# RK3566_FLASH_SD_SARADC.net
KiCad netlist of a schematic drawn in Altium Designer
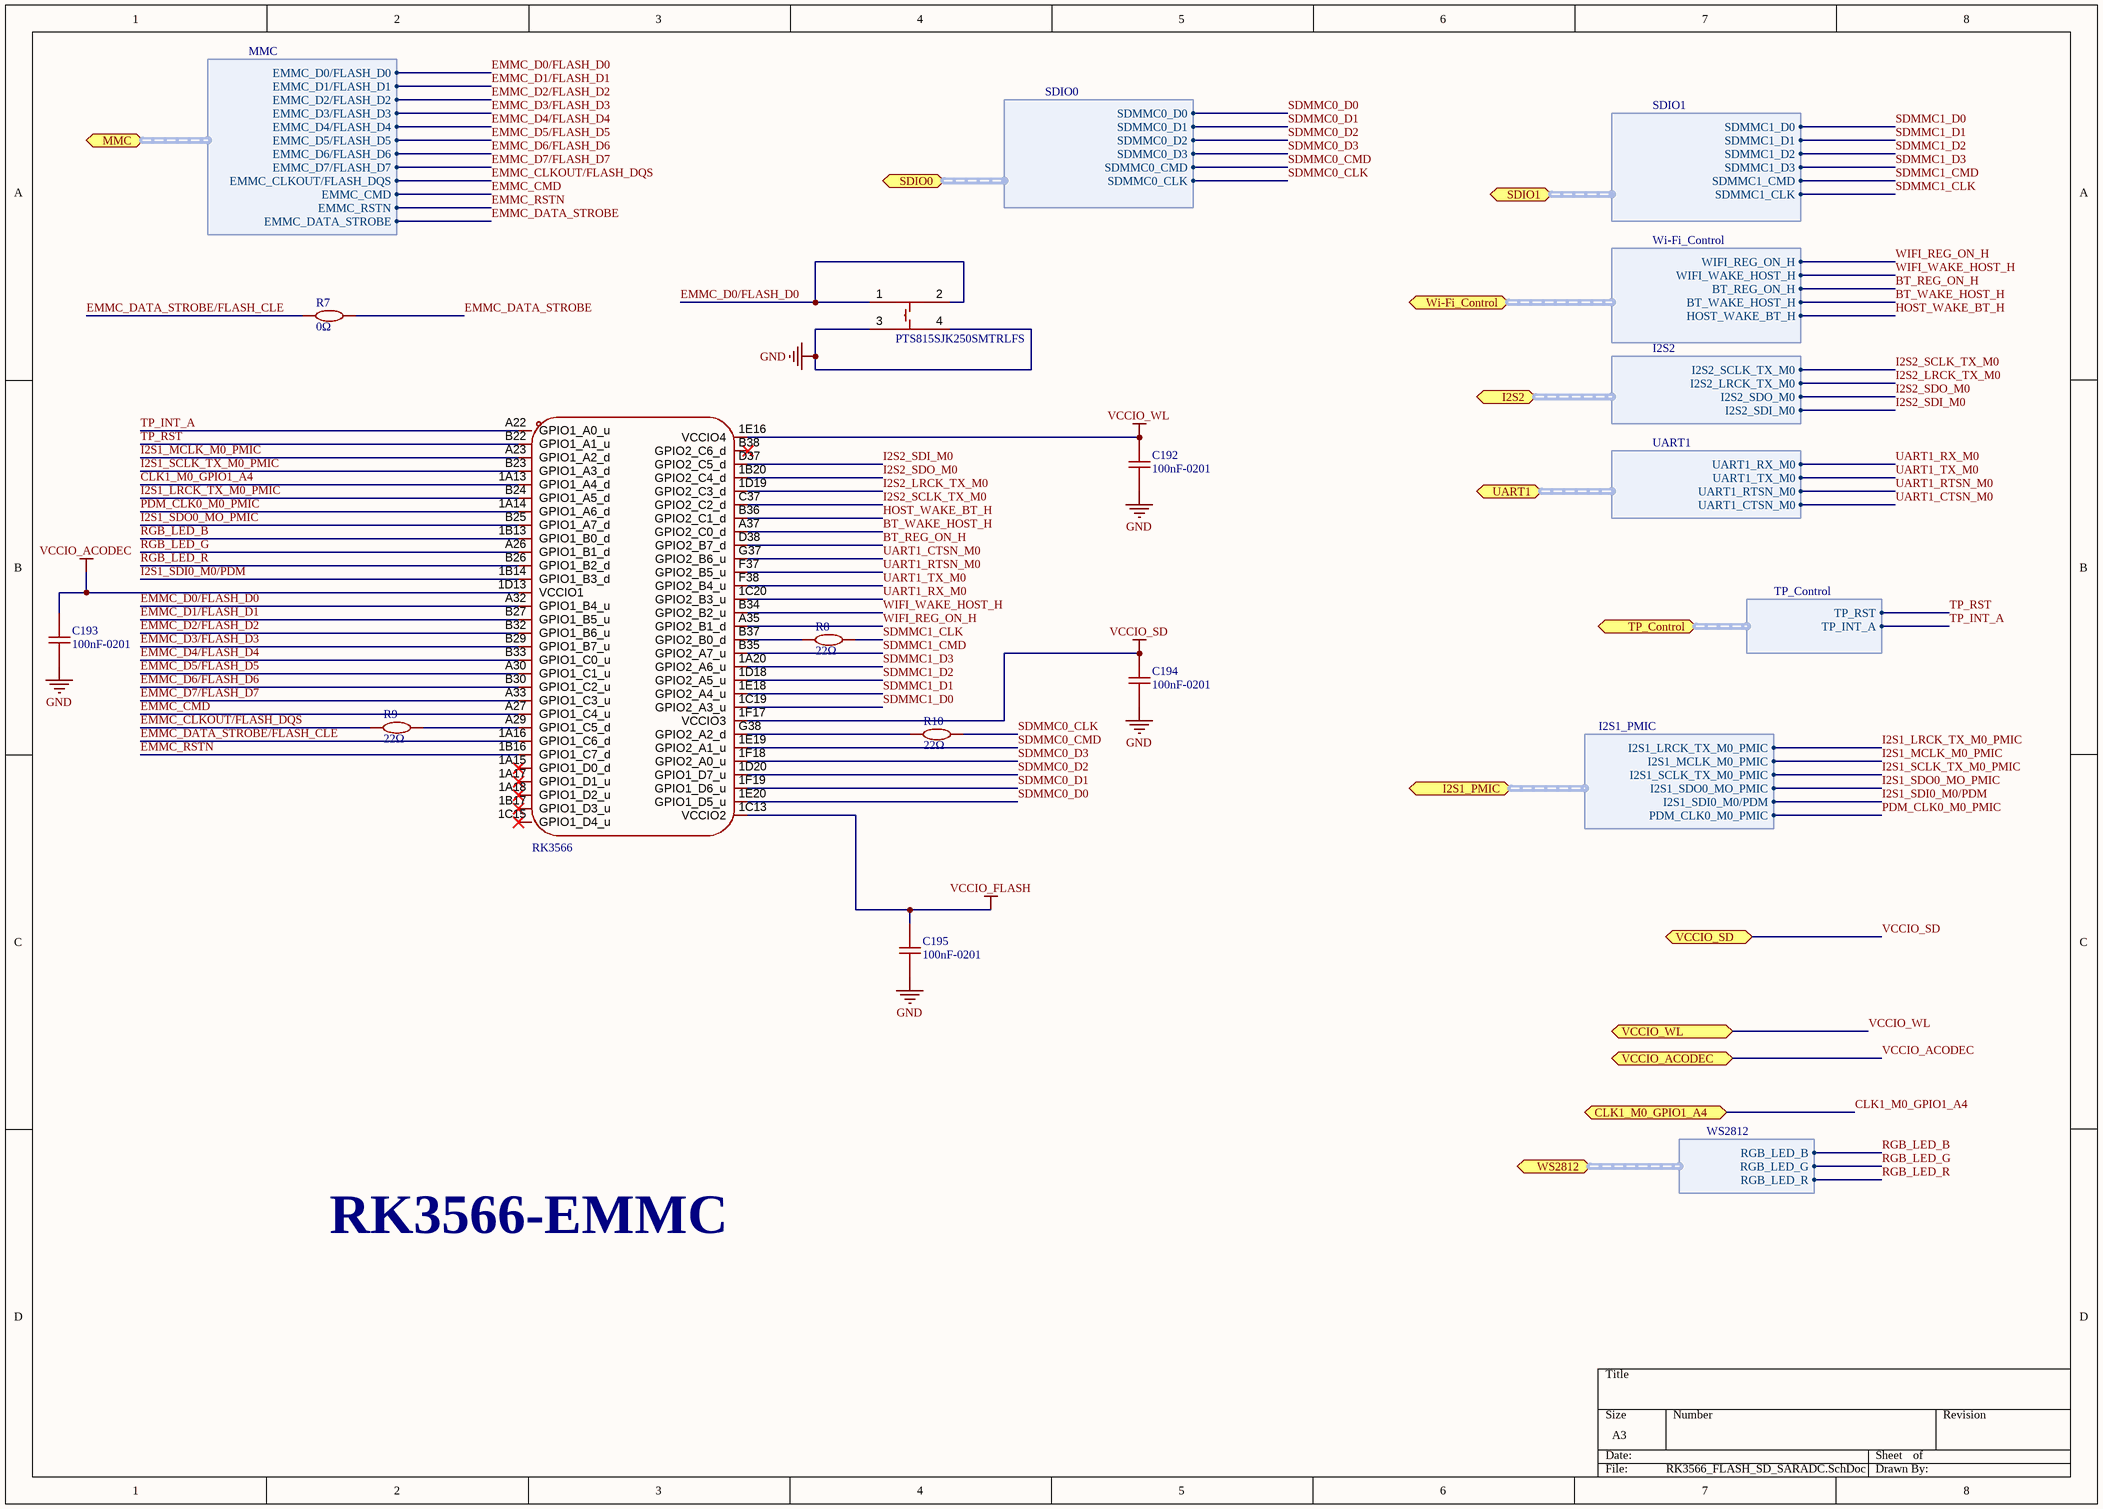
[diagram p0: RK3566_FLASH_SD_SARADC.SchDoc]

(export (version "E")
  (design (tool "Eeschema 10.0.6"))
  (components
    (comp (ref "C192")
      (value "100nF-0201")
      (footprint "C0201")
      (description "CL03A104KO3NNNC")
      (libsource (lib "RLC") (part "100nF-0201"))
    )
    (comp (ref "C193")
      (value "100nF-0201")
      (footprint "C0201")
      (description "CL03A104KO3NNNC")
      (libsource (lib "RLC") (part "100nF-0201"))
    )
    (comp (ref "C194")
      (value "100nF-0201")
      (footprint "C0201")
      (description "CL03A104KO3NNNC")
      (libsource (lib "RLC") (part "100nF-0201"))
    )
    (comp (ref "C195")
      (value "100nF-0201")
      (footprint "C0201")
      (description "CL03A104KO3NNNC")
      (libsource (lib "RLC") (part "100nF-0201"))
    )
    (comp (ref "R7")
      (value "0Ω")
      (footprint "R0402")
      (description "0Ω 62.5mW 50V Thick Film Resistor ±1% 0402 Chip Resistor - Surface Mount ROHS")
      (libsource (lib "RLC") (part "0Ω"))
    )
    (comp (ref "R8")
      (value "22Ω")
      (footprint "R0402")
      (description "62.5mW 33Ω 50V ±100ppm/℃ Thick Film Resistor ±1% 0402 Chip Resistor - Surface Mount ROHS")
      (libsource (lib "RLC") (part "22Ω"))
    )
    (comp (ref "R9")
      (value "22Ω")
      (footprint "R0402")
      (description "62.5mW 33Ω 50V ±100ppm/℃ Thick Film Resistor ±1% 0402 Chip Resistor - Surface Mount ROHS")
      (libsource (lib "RLC") (part "22Ω"))
    )
    (comp (ref "R10")
      (value "22Ω")
      (footprint "R0402")
      (description "62.5mW 33Ω 50V ±100ppm/℃ Thick Film Resistor ±1% 0402 Chip Resistor - Surface Mount ROHS")
      (libsource (lib "RLC") (part "22Ω"))
    )
    (comp (ref "SW4")
      (value "PTS815SJK250SMTRLFS")
      (footprint "SW-SMD_4P-L4.2-W3.3-P2.15-LS5.1")
      (description "4pin 轻触开关 SMD​")
      (libsource (lib "Switch") (part "PTS815SJK250SMTRLFS"))
    )
    (comp (ref "U2")
      (value "RK3566")
      (footprint "BGA-565_L15.5-W14.4-P0.40_RK3566_1")
      (description "BGA-565(15.5x14.4)")
      (libsource (lib "IC") (part "RK3566"))
    )
  )
  (nets
    (net (code "10") (name "/BT_REG_ON_H") (class "Default")
      (node (ref "U2") (pin "D38") (pinfunction "GPIO2_B7_d_D38") (pintype "passive"))
    )
    (net (code "11") (name "/BT_WAKE_HOST_H") (class "Default")
      (node (ref "U2") (pin "A37") (pinfunction "GPIO2_C0_d_A37") (pintype "passive"))
    )
    (net (code "12") (name "/CLK1_M0_GPIO1_A4") (class "Default")
      (node (ref "U2") (pin "1A13") (pinfunction "GPIO1_A4_d_1A13") (pintype "passive"))
    )
    (net (code "13") (name "/EMMC_CLKOUT{slash}FLASH_DQS") (class "Default")
      (node (ref "R9") (pin "1") (pinfunction "1_1") (pintype "passive"))
    )
    (net (code "14") (name "/EMMC_CMD") (class "Default")
      (node (ref "U2") (pin "A27") (pinfunction "GPIO1_C4_u_A27") (pintype "passive"))
    )
    (net (code "15") (name "/EMMC_D0{slash}FLASH_D0") (class "Default")
      (node (ref "SW4") (pin "1") (pinfunction "1_1") (pintype "passive"))
      (node (ref "SW4") (pin "2") (pinfunction "2_2") (pintype "passive"))
      (node (ref "U2") (pin "A32") (pinfunction "GPIO1_B4_u_A32") (pintype "passive"))
    )
    (net (code "16") (name "/EMMC_D1{slash}FLASH_D1") (class "Default")
      (node (ref "U2") (pin "B27") (pinfunction "GPIO1_B5_u_B27") (pintype "passive"))
    )
    (net (code "17") (name "/EMMC_D2{slash}FLASH_D2") (class "Default")
      (node (ref "U2") (pin "B32") (pinfunction "GPIO1_B6_u_B32") (pintype "passive"))
    )
    (net (code "18") (name "/EMMC_D3{slash}FLASH_D3") (class "Default")
      (node (ref "U2") (pin "B29") (pinfunction "GPIO1_B7_u_B29") (pintype "passive"))
    )
    (net (code "19") (name "/EMMC_D4{slash}FLASH_D4") (class "Default")
      (node (ref "U2") (pin "B33") (pinfunction "GPIO1_C0_u_B33") (pintype "passive"))
    )
    (net (code "20") (name "/EMMC_D5{slash}FLASH_D5") (class "Default")
      (node (ref "U2") (pin "A30") (pinfunction "GPIO1_C1_u_A30") (pintype "passive"))
    )
    (net (code "21") (name "/EMMC_D6{slash}FLASH_D6") (class "Default")
      (node (ref "U2") (pin "B30") (pinfunction "GPIO1_C2_u_B30") (pintype "passive"))
    )
    (net (code "22") (name "/EMMC_D7{slash}FLASH_D7") (class "Default")
      (node (ref "U2") (pin "A33") (pinfunction "GPIO1_C3_u_A33") (pintype "passive"))
    )
    (net (code "23") (name "/EMMC_DATA_STROBE") (class "Default")
      (node (ref "R7") (pin "2") (pinfunction "2_2") (pintype "passive"))
    )
    (net (code "24") (name "/EMMC_DATA_STROBE{slash}FLASH_CLE") (class "Default")
      (node (ref "R7") (pin "1") (pinfunction "1_1") (pintype "passive"))
      (node (ref "U2") (pin "1A16") (pinfunction "GPIO1_C6_d_1A16") (pintype "passive"))
    )
    (net (code "25") (name "/EMMC_RSTN") (class "Default")
      (node (ref "U2") (pin "1B16") (pinfunction "GPIO1_C7_d_1B16") (pintype "passive"))
    )
    (net (code "26") (name "/HOST_WAKE_BT_H") (class "Default")
      (node (ref "U2") (pin "B36") (pinfunction "GPIO2_C1_d_B36") (pintype "passive"))
    )
    (net (code "27") (name "/I2S1_LRCK_TX_M0_PMIC") (class "Default")
      (node (ref "U2") (pin "B24") (pinfunction "GPIO1_A5_d_B24") (pintype "passive"))
    )
    (net (code "28") (name "/I2S1_MCLK_M0_PMIC") (class "Default")
      (node (ref "U2") (pin "A23") (pinfunction "GPIO1_A2_d_A23") (pintype "passive"))
    )
    (net (code "29") (name "/I2S1_SCLK_TX_M0_PMIC") (class "Default")
      (node (ref "U2") (pin "B23") (pinfunction "GPIO1_A3_d_B23") (pintype "passive"))
    )
    (net (code "30") (name "/I2S1_SDI0_M0{slash}PDM") (class "Default")
      (node (ref "U2") (pin "1B14") (pinfunction "GPIO1_B3_d_1B14") (pintype "passive"))
    )
    (net (code "31") (name "/I2S1_SDO0_MO_PMIC") (class "Default")
      (node (ref "U2") (pin "B25") (pinfunction "GPIO1_A7_d_B25") (pintype "passive"))
    )
    (net (code "32") (name "/I2S2_LRCK_TX_M0") (class "Default")
      (node (ref "U2") (pin "1D19") (pinfunction "GPIO2_C3_d_1D19") (pintype "passive"))
    )
    (net (code "33") (name "/I2S2_SCLK_TX_M0") (class "Default")
      (node (ref "U2") (pin "C37") (pinfunction "GPIO2_C2_d_C37") (pintype "passive"))
    )
    (net (code "34") (name "/I2S2_SDI_M0") (class "Default")
      (node (ref "U2") (pin "D37") (pinfunction "GPIO2_C5_d_D37") (pintype "passive"))
    )
    (net (code "35") (name "/I2S2_SDO_M0") (class "Default")
      (node (ref "U2") (pin "1B20") (pinfunction "GPIO2_C4_d_1B20") (pintype "passive"))
    )
    (net (code "36") (name "/PDM_CLK0_M0_PMIC") (class "Default")
      (node (ref "U2") (pin "1A14") (pinfunction "GPIO1_A6_d_1A14") (pintype "passive"))
    )
    (net (code "37") (name "/RGB_LED_B") (class "Default")
      (node (ref "U2") (pin "1B13") (pinfunction "GPIO1_B0_d_1B13") (pintype "passive"))
    )
    (net (code "38") (name "/RGB_LED_G") (class "Default")
      (node (ref "U2") (pin "A26") (pinfunction "GPIO1_B1_d_A26") (pintype "passive"))
    )
    (net (code "39") (name "/RGB_LED_R") (class "Default")
      (node (ref "U2") (pin "B26") (pinfunction "GPIO1_B2_d_B26") (pintype "passive"))
    )
    (net (code "40") (name "/SDMMC0_CLK") (class "Default")
      (node (ref "R10") (pin "2") (pinfunction "2_2") (pintype "passive"))
    )
    (net (code "41") (name "/SDMMC0_CMD") (class "Default")
      (node (ref "U2") (pin "1E19") (pinfunction "GPIO2_A1_u_1E19") (pintype "passive"))
    )
    (net (code "42") (name "/SDMMC0_D0") (class "Default")
      (node (ref "U2") (pin "1E20") (pinfunction "GPIO1_D5_u_1E20") (pintype "passive"))
    )
    (net (code "43") (name "/SDMMC0_D1") (class "Default")
      (node (ref "U2") (pin "1F19") (pinfunction "GPIO1_D6_u_1F19") (pintype "passive"))
    )
    (net (code "44") (name "/SDMMC0_D2") (class "Default")
      (node (ref "U2") (pin "1D20") (pinfunction "GPIO1_D7_u_1D20") (pintype "passive"))
    )
    (net (code "45") (name "/SDMMC0_D3") (class "Default")
      (node (ref "U2") (pin "1F18") (pinfunction "GPIO2_A0_u_1F18") (pintype "passive"))
    )
    (net (code "46") (name "/SDMMC1_CLK") (class "Default")
      (node (ref "R8") (pin "2") (pinfunction "2_2") (pintype "passive"))
    )
    (net (code "47") (name "/SDMMC1_CMD") (class "Default")
      (node (ref "U2") (pin "B35") (pinfunction "GPIO2_A7_u_B35") (pintype "passive"))
    )
    (net (code "48") (name "/SDMMC1_D0") (class "Default")
      (node (ref "U2") (pin "1C19") (pinfunction "GPIO2_A3_u_1C19") (pintype "passive"))
    )
    (net (code "49") (name "/SDMMC1_D1") (class "Default")
      (node (ref "U2") (pin "1E18") (pinfunction "GPIO2_A4_u_1E18") (pintype "passive"))
    )
    (net (code "50") (name "/SDMMC1_D2") (class "Default")
      (node (ref "U2") (pin "1D18") (pinfunction "GPIO2_A5_u_1D18") (pintype "passive"))
    )
    (net (code "51") (name "/SDMMC1_D3") (class "Default")
      (node (ref "U2") (pin "1A20") (pinfunction "GPIO2_A6_u_1A20") (pintype "passive"))
    )
    (net (code "52") (name "/TP_INT_A") (class "Default")
      (node (ref "U2") (pin "A22") (pinfunction "GPIO1_A0_u_A22") (pintype "passive"))
    )
    (net (code "53") (name "/TP_RST") (class "Default")
      (node (ref "U2") (pin "B22") (pinfunction "GPIO1_A1_u_B22") (pintype "passive"))
    )
    (net (code "54") (name "/UART1_CTSN_M0") (class "Default")
      (node (ref "U2") (pin "G37") (pinfunction "GPIO2_B6_u_G37") (pintype "passive"))
    )
    (net (code "55") (name "/UART1_RTSN_M0") (class "Default")
      (node (ref "U2") (pin "F37") (pinfunction "GPIO2_B5_u_F37") (pintype "passive"))
    )
    (net (code "56") (name "/UART1_RX_M0") (class "Default")
      (node (ref "U2") (pin "1C20") (pinfunction "GPIO2_B3_u_1C20") (pintype "passive"))
    )
    (net (code "57") (name "/UART1_TX_M0") (class "Default")
      (node (ref "U2") (pin "F38") (pinfunction "GPIO2_B4_u_F38") (pintype "passive"))
    )
    (net (code "58") (name "/WIFI_REG_ON_H") (class "Default")
      (node (ref "U2") (pin "A35") (pinfunction "GPIO2_B1_d_A35") (pintype "passive"))
    )
    (net (code "59") (name "/WIFI_WAKE_HOST_H") (class "Default")
      (node (ref "U2") (pin "B34") (pinfunction "GPIO2_B2_u_B34") (pintype "passive"))
    )
    (net (code "69") (name "GND") (class "Default")
      (node (ref "C192") (pin "1") (pinfunction "1_1") (pintype "passive"))
      (node (ref "C193") (pin "1") (pinfunction "1_1") (pintype "passive"))
      (node (ref "C194") (pin "1") (pinfunction "1_1") (pintype "passive"))
      (node (ref "C195") (pin "1") (pinfunction "1_1") (pintype "passive"))
      (node (ref "SW4") (pin "3") (pinfunction "3_3") (pintype "passive"))
      (node (ref "SW4") (pin "4") (pinfunction "4_4") (pintype "passive"))
    )
    (net (code "70") (name "Net-(U2E-GPIO1_C5_d)") (class "Default")
      (node (ref "R9") (pin "2") (pinfunction "2_2") (pintype "passive"))
      (node (ref "U2") (pin "A29") (pinfunction "GPIO1_C5_d_A29") (pintype "passive"))
    )
    (net (code "71") (name "Net-(U2E-GPIO2_A2_d)") (class "Default")
      (node (ref "R10") (pin "1") (pinfunction "1_1") (pintype "passive"))
      (node (ref "U2") (pin "G38") (pinfunction "GPIO2_A2_d_G38") (pintype "passive"))
    )
    (net (code "72") (name "Net-(U2E-GPIO2_B0_d)") (class "Default")
      (node (ref "R8") (pin "1") (pinfunction "1_1") (pintype "passive"))
      (node (ref "U2") (pin "B37") (pinfunction "GPIO2_B0_d_B37") (pintype "passive"))
    )
    (net (code "73") (name "VCCIO_ACODEC") (class "Default")
      (node (ref "C193") (pin "2") (pinfunction "2_2") (pintype "passive"))
      (node (ref "U2") (pin "1D13") (pinfunction "VCCIO1_1D13") (pintype "passive"))
    )
    (net (code "74") (name "VCCIO_FLASH") (class "Default")
      (node (ref "C195") (pin "2") (pinfunction "2_2") (pintype "passive"))
      (node (ref "U2") (pin "1C13") (pinfunction "VCCIO2_1C13") (pintype "passive"))
    )
    (net (code "75") (name "VCCIO_SD") (class "Default")
      (node (ref "C194") (pin "2") (pinfunction "2_2") (pintype "passive"))
      (node (ref "U2") (pin "1F17") (pinfunction "VCCIO3_1F17") (pintype "passive"))
    )
    (net (code "76") (name "VCCIO_WL") (class "Default")
      (node (ref "C192") (pin "2") (pinfunction "2_2") (pintype "passive"))
      (node (ref "U2") (pin "1E16") (pinfunction "VCCIO4_1E16") (pintype "passive"))
    )
    (net (code "77") (name "unconnected-(U2E-GPIO1_D0_d-Pad1A15)") (class "Default")
      (node (ref "U2") (pin "1A15") (pinfunction "GPIO1_D0_d_1A15") (pintype "passive+no_connect"))
    )
    (net (code "78") (name "unconnected-(U2E-GPIO1_D1_u-Pad1A17)") (class "Default")
      (node (ref "U2") (pin "1A17") (pinfunction "GPIO1_D1_u_1A17") (pintype "passive+no_connect"))
    )
    (net (code "79") (name "unconnected-(U2E-GPIO1_D2_u-Pad1A18)") (class "Default")
      (node (ref "U2") (pin "1A18") (pinfunction "GPIO1_D2_u_1A18") (pintype "passive+no_connect"))
    )
    (net (code "80") (name "unconnected-(U2E-GPIO1_D3_u-Pad1B17)") (class "Default")
      (node (ref "U2") (pin "1B17") (pinfunction "GPIO1_D3_u_1B17") (pintype "passive+no_connect"))
    )
    (net (code "81") (name "unconnected-(U2E-GPIO1_D4_u-Pad1C15)") (class "Default")
      (node (ref "U2") (pin "1C15") (pinfunction "GPIO1_D4_u_1C15") (pintype "passive+no_connect"))
    )
    (net (code "82") (name "unconnected-(U2E-GPIO2_C6_d-PadB38)") (class "Default")
      (node (ref "U2") (pin "B38") (pinfunction "GPIO2_C6_d_B38") (pintype "passive+no_connect"))
    )
  )
)
